# usb_HUB.net
KiCad netlist of a schematic drawn in Altium Designer
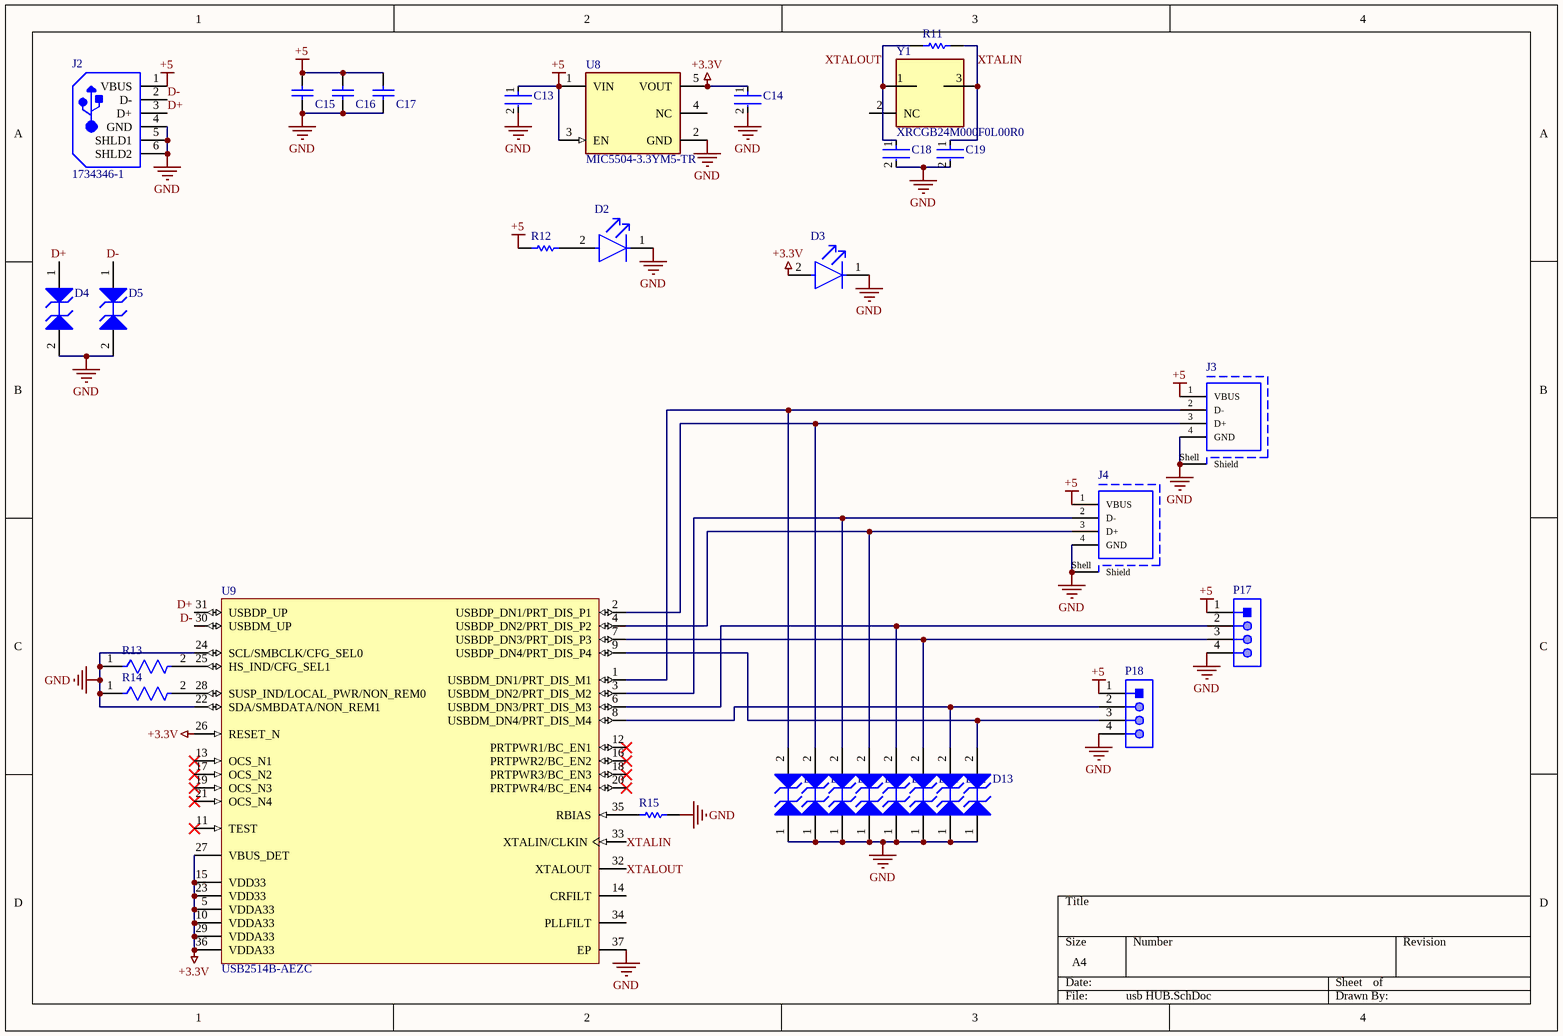
[diagram p0: usb HUB.SchDoc]

(export (version "E")
  (design (tool "Eeschema 10.0.6"))
  (components
    (comp (ref "C13")
      (value "CL31B105MAHNNNE")
      (footprint "FP-CL31-IPC_B")
      (description "Cap Ceramic 1uF 25V X7R ±20% SMD 1206 +125°C Embossed T/R")
      (fields (field (name "TOLERANCE") "20%"))
      (libsource (lib "Altium Content Vault") (part "b4654b650e69147ec39a6b967a45e02"))
    )
    (comp (ref "C14")
      (value "CL31B105MAHNNNE")
      (footprint "FP-CL31-IPC_B")
      (description "Cap Ceramic 1uF 25V X7R ±20% SMD 1206 +125°C Embossed T/R")
      (fields (field (name "TOLERANCE") "20%"))
      (libsource (lib "Altium Content Vault") (part "b4654b650e69147ec39a6b967a45e02"))
    )
    (comp (ref "C15")
      (value "12061Z475KAT2A")
      (footprint "CAPC3216X190X50ML20T25")
      (description "Chip Capacitor, 4.7 uF, +/- 10%, 100 V, -55 to 125 degC, 1206 (3216 Metric), RoHS, Tape and Reel")
      (fields (field (name "MANUFACTURER") "AVX"))
      (libsource (lib "Altium Content Vault") (part "CAP-NP-2"))
    )
    (comp (ref "C16")
      (value "12061Z475KAT2A")
      (footprint "CAPC3216X190X50ML20T25")
      (description "Chip Capacitor, 4.7 uF, +/- 10%, 100 V, -55 to 125 degC, 1206 (3216 Metric), RoHS, Tape and Reel")
      (fields (field (name "MANUFACTURER") "AVX"))
      (libsource (lib "Altium Content Vault") (part "CAP-NP-2"))
    )
    (comp (ref "C17")
      (value "12061Z475KAT2A")
      (footprint "CAPC3216X190X50ML20T25")
      (description "Chip Capacitor, 4.7 uF, +/- 10%, 100 V, -55 to 125 degC, 1206 (3216 Metric), RoHS, Tape and Reel")
      (fields (field (name "MANUFACTURER") "AVX"))
      (libsource (lib "Altium Content Vault") (part "CAP-NP-2"))
    )
    (comp (ref "C18")
      (value "GRM31A7U2J180JW31D")
      (footprint "FP-GRM31A-0_2-e0_3_0_95-IPC_B")
      (description "Chip Multilayer Ceramic Capacitors for General Purpose, 1206, 18pF, U2J, -750ppm/°C, 5%, 630V")
      (fields (field (name "TOLERANCE") "5%"))
      (libsource (lib "Altium Content Vault") (part "b4654b650e69147ec39a6b967a45e02"))
    )
    (comp (ref "C19")
      (value "GRM31A7U2J180JW31D")
      (footprint "FP-GRM31A-0_2-e0_3_0_95-IPC_B")
      (description "Chip Multilayer Ceramic Capacitors for General Purpose, 1206, 18pF, U2J, -750ppm/°C, 5%, 630V")
      (fields (field (name "TOLERANCE") "5%"))
      (libsource (lib "Altium Content Vault") (part "b4654b650e69147ec39a6b967a45e02"))
    )
    (comp (ref "D2")
      (value "APTD3216CGCK")
      (footprint "FP-APTD3216CGCK-MFG")
      (description "LED GREEN CLEAR 2SMD")
      (libsource (lib "Altium Content Vault") (part "8706943c75ba83719d021d2fdc84c58"))
    )
    (comp (ref "D3")
      (value "APTD3216CGCK")
      (footprint "FP-APTD3216CGCK-MFG")
      (description "LED GREEN CLEAR 2SMD")
      (libsource (lib "Altium Content Vault") (part "8706943c75ba83719d021d2fdc84c58"))
    )
    (comp (ref "D4")
      (value "ESD9B3.3ST5G")
      (footprint "ONSC-SOD-923-2-514AB-01_V")
      (fields (field (name "MANUFACTURER") "On Semiconductor"))
      (libsource (lib "Altium Content Vault") (part "ONSC-A1A2-2"))
    )
    (comp (ref "D5")
      (value "ESD9B3.3ST5G")
      (footprint "ONSC-SOD-923-2-514AB-01_V")
      (fields (field (name "MANUFACTURER") "On Semiconductor"))
      (libsource (lib "Altium Content Vault") (part "ONSC-A1A2-2"))
    )
    (comp (ref "D6")
      (value "ESD9B3.3ST5G")
      (footprint "ONSC-SOD-923-2-514AB-01_V")
      (fields (field (name "MANUFACTURER") "On Semiconductor"))
      (libsource (lib "Altium Content Vault") (part "ONSC-A1A2-2"))
    )
    (comp (ref "D7")
      (value "ESD9B3.3ST5G")
      (footprint "ONSC-SOD-923-2-514AB-01_V")
      (fields (field (name "MANUFACTURER") "On Semiconductor"))
      (libsource (lib "Altium Content Vault") (part "ONSC-A1A2-2"))
    )
    (comp (ref "D8")
      (value "ESD9B3.3ST5G")
      (footprint "ONSC-SOD-923-2-514AB-01_V")
      (fields (field (name "MANUFACTURER") "On Semiconductor"))
      (libsource (lib "Altium Content Vault") (part "ONSC-A1A2-2"))
    )
    (comp (ref "D9")
      (value "ESD9B3.3ST5G")
      (footprint "ONSC-SOD-923-2-514AB-01_V")
      (fields (field (name "MANUFACTURER") "On Semiconductor"))
      (libsource (lib "Altium Content Vault") (part "ONSC-A1A2-2"))
    )
    (comp (ref "D10")
      (value "ESD9B3.3ST5G")
      (footprint "ONSC-SOD-923-2-514AB-01_V")
      (fields (field (name "MANUFACTURER") "On Semiconductor"))
      (libsource (lib "Altium Content Vault") (part "ONSC-A1A2-2"))
    )
    (comp (ref "D11")
      (value "ESD9B3.3ST5G")
      (footprint "ONSC-SOD-923-2-514AB-01_V")
      (fields (field (name "MANUFACTURER") "On Semiconductor"))
      (libsource (lib "Altium Content Vault") (part "ONSC-A1A2-2"))
    )
    (comp (ref "D12")
      (value "ESD9B3.3ST5G")
      (footprint "ONSC-SOD-923-2-514AB-01_V")
      (fields (field (name "MANUFACTURER") "On Semiconductor"))
      (libsource (lib "Altium Content Vault") (part "ONSC-A1A2-2"))
    )
    (comp (ref "D13")
      (value "ESD9B3.3ST5G")
      (footprint "ONSC-SOD-923-2-514AB-01_V")
      (fields (field (name "MANUFACTURER") "On Semiconductor"))
      (libsource (lib "Altium Content Vault") (part "ONSC-A1A2-2"))
    )
    (comp (ref "J2")
      (value "1734346-1")
      (footprint "TECO-1734346-1_V")
      (description "USB-B Receptacle Connector, Height 10.87 mm, 0 to 50 degC, RoHS, Tray")
      (fields (field (name "MANUFACTURER") "TE Connectivity"))
      (libsource (lib "Altium Content Vault") (part "USB-4-2SHLD"))
    )
    (comp (ref "J3")
      (value "629104190121")
      (footprint "629104190121")
      (description "USB 2.0 Type A Receptacle WR-COM, Horizontal, SMT, Short Type with Pads and Pegs")
      (fields (field (name "MANUFACTURER") "Wurth Elektronik") (field (name "PUBLISHER") "WurthElektronik"))
      (libsource (lib "Altium Content Vault") (part "WE-USB-4-1SHLD"))
    )
    (comp (ref "J4")
      (value "629104190121")
      (footprint "629104190121")
      (description "USB 2.0 Type A Receptacle WR-COM, Horizontal, SMT, Short Type with Pads and Pegs")
      (fields (field (name "MANUFACTURER") "Wurth Elektronik") (field (name "PUBLISHER") "WurthElektronik"))
      (libsource (lib "Altium Content Vault") (part "WE-USB-4-1SHLD"))
    )
    (comp (ref "P17")
      (value "61300411121")
      (footprint "61300411121")
      (description "THT Vertical Pin Header WR-PHD, Pitch 2.54 mm, Single Row, 4 pins")
      (fields (field (name "MANUFACTURER") "Wurth Elektronik") (field (name "PUBLISHER") "WurthElektronik"))
      (libsource (lib "Altium Content Vault") (part "WE-CN-1P-M-R4"))
    )
    (comp (ref "P18")
      (value "61300411121")
      (footprint "61300411121")
      (description "THT Vertical Pin Header WR-PHD, Pitch 2.54 mm, Single Row, 4 pins")
      (fields (field (name "MANUFACTURER") "Wurth Elektronik") (field (name "PUBLISHER") "WurthElektronik"))
      (libsource (lib "Altium Content Vault") (part "WE-CN-1P-M-R4"))
    )
    (comp (ref "R11")
      (value "ERJ-8ENF1004V")
      (footprint "RESC3216X70X50NL05T20")
      (fields (field (name "MANUFACTURER") "Panasonic"))
      (libsource (lib "Altium Content Vault") (part "RES"))
    )
    (comp (ref "R12")
      (value "ERJ8ENF2203V")
      (footprint "RESC3216X70X50LL05T20")
      (fields (field (name "MANUFACTURER") "Panasonic"))
      (libsource (lib "Altium Content Vault") (part "RES"))
    )
    (comp (ref "R13")
      (value "CRCW120656K0FKEA")
      (footprint "FP-CRCW1206-e3-IPC_C")
      (description "RES Thick Film, 56kΩ, 1%, 0.25W, 100ppm/°C, 1206")
      (fields (field (name "TOLERANCE") "1%"))
      (libsource (lib "Altium Content Vault") (part "1029c3af85768c4190bb7ad29bc67b5"))
    )
    (comp (ref "R14")
      (value "CRCW120656K0FKEA")
      (footprint "FP-CRCW1206-e3-IPC_C")
      (description "RES Thick Film, 56kΩ, 1%, 0.25W, 100ppm/°C, 1206")
      (fields (field (name "TOLERANCE") "1%"))
      (libsource (lib "Altium Content Vault") (part "1029c3af85768c4190bb7ad29bc67b5"))
    )
    (comp (ref "R15")
      (value "ERJ-8GEYJ123V")
      (footprint "RESC3216X70X50NL05T20")
      (fields (field (name "MANUFACTURER") "Panasonic"))
      (libsource (lib "Altium Content Vault") (part "RES"))
    )
    (comp (ref "U8")
      (value "MIC5504-3.3YM5-TR")
      (footprint "FP-SOT23-5LD-PL-1-MFG")
      (description "IC REG LINEAR 3.3V 300MA SOT23-5")
      (libsource (lib "Altium Content Vault") (part "96048095611b4a9579e1e315950d302"))
    )
    (comp (ref "U9")
      (value "USB2514B-AEZC")
      (footprint "Components - 28.12.20 - 14.59:MCHP-QFN-36_V")
      (description "USB 2.0 High-Speed Hub Controller, 4 Ports, 3 to 3.6 V, 0 to 85 degC, 36-Pin QFN, RoHS, Tray")
      (fields (field (name "MANUFACTURER") "Microchip"))
      (libsource (lib "Deej Board") (part "CMP-2000-05217-1"))
    )
    (comp (ref "Y1")
      (value "Crys_Murata_XRCGB24M000F0L00R0_eec")
      (footprint "Crys_Murata_XRCGB24M000F0L00R0_eec_0:Murata_XRCGB24M000F0L00R0_0")
      (description "CRYS 24MHz ±100ppm Crystal 6pF 150 Ohm -30°C ~ 85°C Surface Mount 4-SMD, No Lead")
      (fields
        (field (name "MANUFACTURER") "Murata")
        (field (name "MOUSER PART NUMBER") "81-XRCGB24M000F0L0R0")
        (field (name "PART NUMBER") "XRCGB24M000F0L00R0")
      )
      (libsource (lib "Crys_Murata_XRCGB24M000F0L00R0_eec") (part "Crys_Murata_XRCGB24M000F0L00R0_eec"))
    )
  )
  (nets
    (net (code "1") (name "+3.3V") (class "Default")
      (node (ref "C14") (pin "1") (pinfunction "1_1") (pintype "passive"))
      (node (ref "D3") (pin "2") (pinfunction "A_2") (pintype "passive"))
      (node (ref "U8") (pin "5") (pinfunction "VOUT_5") (pintype "power_in"))
      (node (ref "U9") (pin "10") (pinfunction "VDDA33_10") (pintype "power_in"))
      (node (ref "U9") (pin "15") (pinfunction "VDD33_15") (pintype "power_in"))
      (node (ref "U9") (pin "23") (pinfunction "VDD33_23") (pintype "power_in"))
      (node (ref "U9") (pin "26") (pinfunction "RESET_N_26") (pintype "input"))
      (node (ref "U9") (pin "27") (pinfunction "VBUS_DET_27") (pintype "power_in"))
      (node (ref "U9") (pin "29") (pinfunction "VDDA33_29") (pintype "power_in"))
      (node (ref "U9") (pin "36") (pinfunction "VDDA33_36") (pintype "power_in"))
      (node (ref "U9") (pin "5") (pinfunction "VDDA33_5") (pintype "power_in"))
    )
    (net (code "2") (name "+5") (class "Default")
      (node (ref "C13") (pin "1") (pinfunction "1_1") (pintype "passive"))
      (node (ref "C15") (pin "1") (pinfunction "1_1") (pintype "passive"))
      (node (ref "C16") (pin "1") (pinfunction "1_1") (pintype "passive"))
      (node (ref "C17") (pin "1") (pinfunction "1_1") (pintype "passive"))
      (node (ref "J2") (pin "1") (pinfunction "VBUS_1") (pintype "passive"))
      (node (ref "J3") (pin "1") (pinfunction "VBUS_1") (pintype "passive"))
      (node (ref "J4") (pin "1") (pinfunction "VBUS_1") (pintype "passive"))
      (node (ref "P17") (pin "1") (pinfunction "1_1") (pintype "passive"))
      (node (ref "P18") (pin "1") (pinfunction "1_1") (pintype "passive"))
      (node (ref "R12") (pin "1") (pinfunction "1_1") (pintype "passive"))
      (node (ref "U8") (pin "1") (pinfunction "VIN_1") (pintype "power_in"))
      (node (ref "U8") (pin "3") (pinfunction "EN_3") (pintype "input"))
    )
    (net (code "3") (name "/D+") (class "Default")
      (node (ref "D4") (pin "1") (pinfunction "A1_1") (pintype "passive"))
      (node (ref "J2") (pin "3") (pinfunction "D+_3") (pintype "passive"))
      (node (ref "U9") (pin "31") (pinfunction "USBDP_UP_31") (pintype "bidirectional"))
    )
    (net (code "4") (name "/D-") (class "Default")
      (node (ref "D5") (pin "1") (pinfunction "A1_1") (pintype "passive"))
      (node (ref "J2") (pin "2") (pinfunction "D-_2") (pintype "passive"))
      (node (ref "U9") (pin "30") (pinfunction "USBDM_UP_30") (pintype "bidirectional"))
    )
    (net (code "5") (name "/XTALIN") (class "Default")
      (node (ref "C19") (pin "1") (pinfunction "1_1") (pintype "passive"))
      (node (ref "R11") (pin "2") (pinfunction "2_2") (pintype "passive"))
      (node (ref "U9") (pin "33") (pinfunction "XTALIN/CLKIN_33") (pintype "input"))
      (node (ref "Y1") (pin "3") (pinfunction "2_Crystal_Terminal_3") (pintype "passive"))
    )
    (net (code "6") (name "/XTALOUT") (class "Default")
      (node (ref "C18") (pin "1") (pinfunction "1_1") (pintype "passive"))
      (node (ref "R11") (pin "1") (pinfunction "1_1") (pintype "passive"))
      (node (ref "U9") (pin "32") (pinfunction "XTALOUT_32") (pintype "passive"))
      (node (ref "Y1") (pin "1") (pinfunction "1_Crystal_Terminal_1") (pintype "passive"))
    )
    (net (code "7") (name "GND") (class "Default")
      (node (ref "C13") (pin "2") (pinfunction "2_2") (pintype "passive"))
      (node (ref "C14") (pin "2") (pinfunction "2_2") (pintype "passive"))
      (node (ref "C15") (pin "2") (pinfunction "2_2") (pintype "passive"))
      (node (ref "C16") (pin "2") (pinfunction "2_2") (pintype "passive"))
      (node (ref "C17") (pin "2") (pinfunction "2_2") (pintype "passive"))
      (node (ref "C18") (pin "2") (pinfunction "2_2") (pintype "passive"))
      (node (ref "C19") (pin "2") (pinfunction "2_2") (pintype "passive"))
      (node (ref "D10") (pin "1") (pinfunction "A1_1") (pintype "passive"))
      (node (ref "D11") (pin "1") (pinfunction "A1_1") (pintype "passive"))
      (node (ref "D12") (pin "1") (pinfunction "A1_1") (pintype "passive"))
      (node (ref "D13") (pin "1") (pinfunction "A1_1") (pintype "passive"))
      (node (ref "D2") (pin "1") (pinfunction "C_1") (pintype "passive"))
      (node (ref "D3") (pin "1") (pinfunction "C_1") (pintype "passive"))
      (node (ref "D4") (pin "2") (pinfunction "A2_2") (pintype "passive"))
      (node (ref "D5") (pin "2") (pinfunction "A2_2") (pintype "passive"))
      (node (ref "D6") (pin "1") (pinfunction "A1_1") (pintype "passive"))
      (node (ref "D7") (pin "1") (pinfunction "A1_1") (pintype "passive"))
      (node (ref "D8") (pin "1") (pinfunction "A1_1") (pintype "passive"))
      (node (ref "D9") (pin "1") (pinfunction "A1_1") (pintype "passive"))
      (node (ref "J2") (pin "4") (pinfunction "GND_4") (pintype "passive"))
      (node (ref "J2") (pin "5") (pinfunction "SHLD1_5") (pintype "passive"))
      (node (ref "J2") (pin "6") (pinfunction "SHLD2_6") (pintype "passive"))
      (node (ref "J3") (pin "4") (pinfunction "GND_4") (pintype "passive"))
      (node (ref "J3") (pin "Shell") (pinfunction "Shield_Shell") (pintype "passive"))
      (node (ref "J4") (pin "4") (pinfunction "GND_4") (pintype "passive"))
      (node (ref "J4") (pin "Shell") (pinfunction "Shield_Shell") (pintype "passive"))
      (node (ref "P17") (pin "4") (pinfunction "4_4") (pintype "passive"))
      (node (ref "P18") (pin "4") (pinfunction "4_4") (pintype "passive"))
      (node (ref "R13") (pin "1") (pinfunction "1_1") (pintype "passive"))
      (node (ref "R14") (pin "1") (pinfunction "1_1") (pintype "passive"))
      (node (ref "R15") (pin "2") (pinfunction "2_2") (pintype "passive"))
      (node (ref "U8") (pin "2") (pinfunction "GND_2") (pintype "power_in"))
      (node (ref "U9") (pin "22") (pinfunction "SDA/SMBDATA/NON_REM1_22") (pintype "bidirectional"))
      (node (ref "U9") (pin "24") (pinfunction "SCL/SMBCLK/CFG_SEL0_24") (pintype "bidirectional"))
      (node (ref "U9") (pin "37") (pinfunction "EP_37") (pintype "power_in"))
    )
    (net (code "8") (name "Net-(D2-A)") (class "Default")
      (node (ref "D2") (pin "2") (pinfunction "A_2") (pintype "passive"))
      (node (ref "R12") (pin "2") (pinfunction "2_2") (pintype "passive"))
    )
    (net (code "9") (name "Net-(D6-A2)") (class "Default")
      (node (ref "D6") (pin "2") (pinfunction "A2_2") (pintype "passive"))
      (node (ref "J3") (pin "2") (pinfunction "D-_2") (pintype "passive"))
      (node (ref "U9") (pin "1") (pinfunction "USBDM_DN1/PRT_DIS_M1_1") (pintype "bidirectional"))
    )
    (net (code "10") (name "Net-(D7-A2)") (class "Default")
      (node (ref "D7") (pin "2") (pinfunction "A2_2") (pintype "passive"))
      (node (ref "J3") (pin "3") (pinfunction "D+_3") (pintype "passive"))
      (node (ref "U9") (pin "2") (pinfunction "USBDP_DN1/PRT_DIS_P1_2") (pintype "bidirectional"))
    )
    (net (code "11") (name "Net-(D8-A2)") (class "Default")
      (node (ref "D8") (pin "2") (pinfunction "A2_2") (pintype "passive"))
      (node (ref "J4") (pin "2") (pinfunction "D-_2") (pintype "passive"))
      (node (ref "U9") (pin "3") (pinfunction "USBDM_DN2/PRT_DIS_M2_3") (pintype "bidirectional"))
    )
    (net (code "12") (name "Net-(D9-A2)") (class "Default")
      (node (ref "D9") (pin "2") (pinfunction "A2_2") (pintype "passive"))
      (node (ref "J4") (pin "3") (pinfunction "D+_3") (pintype "passive"))
      (node (ref "U9") (pin "4") (pinfunction "USBDP_DN2/PRT_DIS_P2_4") (pintype "bidirectional"))
    )
    (net (code "13") (name "Net-(D10-A2)") (class "Default")
      (node (ref "D10") (pin "2") (pinfunction "A2_2") (pintype "passive"))
      (node (ref "P17") (pin "2") (pinfunction "2_2") (pintype "passive"))
      (node (ref "U9") (pin "6") (pinfunction "USBDM_DN3/PRT_DIS_M3_6") (pintype "bidirectional"))
    )
    (net (code "14") (name "Net-(D11-A2)") (class "Default")
      (node (ref "D11") (pin "2") (pinfunction "A2_2") (pintype "passive"))
      (node (ref "P17") (pin "3") (pinfunction "3_3") (pintype "passive"))
      (node (ref "U9") (pin "7") (pinfunction "USBDP_DN3/PRT_DIS_P3_7") (pintype "bidirectional"))
    )
    (net (code "15") (name "Net-(D12-A2)") (class "Default")
      (node (ref "D12") (pin "2") (pinfunction "A2_2") (pintype "passive"))
      (node (ref "P18") (pin "2") (pinfunction "2_2") (pintype "passive"))
      (node (ref "U9") (pin "8") (pinfunction "USBDM_DN4/PRT_DIS_M4_8") (pintype "bidirectional"))
    )
    (net (code "16") (name "Net-(D13-A2)") (class "Default")
      (node (ref "D13") (pin "2") (pinfunction "A2_2") (pintype "passive"))
      (node (ref "P18") (pin "3") (pinfunction "3_3") (pintype "passive"))
      (node (ref "U9") (pin "9") (pinfunction "USBDP_DN4/PRT_DIS_P4_9") (pintype "bidirectional"))
    )
    (net (code "17") (name "Net-(U9-HS_IND{slash}CFG_SEL1)") (class "Default")
      (node (ref "R13") (pin "2") (pinfunction "2_2") (pintype "passive"))
      (node (ref "U9") (pin "25") (pinfunction "HS_IND/CFG_SEL1_25") (pintype "bidirectional"))
    )
    (net (code "18") (name "Net-(U9-RBIAS)") (class "Default")
      (node (ref "R15") (pin "1") (pinfunction "1_1") (pintype "passive"))
      (node (ref "U9") (pin "35") (pinfunction "RBIAS_35") (pintype "input"))
    )
    (net (code "19") (name "Net-(U9-SUSP_IND{slash}LOCAL_PWR{slash}NON_REM0)") (class "Default")
      (node (ref "R14") (pin "2") (pinfunction "2_2") (pintype "passive"))
      (node (ref "U9") (pin "28") (pinfunction "SUSP_IND/LOCAL_PWR/NON_REM0_28") (pintype "bidirectional"))
    )
    (net (code "20") (name "unconnected-(U8-NC-Pad4)") (class "Default")
      (node (ref "U8") (pin "4") (pinfunction "NC_4") (pintype "passive"))
    )
    (net (code "21") (name "unconnected-(U9-CRFILT-Pad14)") (class "Default")
      (node (ref "U9") (pin "14") (pinfunction "CRFILT_14") (pintype "passive"))
    )
    (net (code "22") (name "unconnected-(U9-OCS_N1-Pad13)") (class "Default")
      (node (ref "U9") (pin "13") (pinfunction "OCS_N1_13") (pintype "input+no_connect"))
    )
    (net (code "23") (name "unconnected-(U9-OCS_N2-Pad17)") (class "Default")
      (node (ref "U9") (pin "17") (pinfunction "OCS_N2_17") (pintype "input+no_connect"))
    )
    (net (code "24") (name "unconnected-(U9-OCS_N3-Pad19)") (class "Default")
      (node (ref "U9") (pin "19") (pinfunction "OCS_N3_19") (pintype "input+no_connect"))
    )
    (net (code "25") (name "unconnected-(U9-OCS_N4-Pad21)") (class "Default")
      (node (ref "U9") (pin "21") (pinfunction "OCS_N4_21") (pintype "input+no_connect"))
    )
    (net (code "26") (name "unconnected-(U9-PLLFILT-Pad34)") (class "Default")
      (node (ref "U9") (pin "34") (pinfunction "PLLFILT_34") (pintype "passive"))
    )
    (net (code "27") (name "unconnected-(U9-PRTPWR1{slash}BC_EN1-Pad12)") (class "Default")
      (node (ref "U9") (pin "12") (pinfunction "PRTPWR1/BC_EN1_12") (pintype "bidirectional+no_connect"))
    )
    (net (code "28") (name "unconnected-(U9-PRTPWR2{slash}BC_EN2-Pad16)") (class "Default")
      (node (ref "U9") (pin "16") (pinfunction "PRTPWR2/BC_EN2_16") (pintype "bidirectional+no_connect"))
    )
    (net (code "29") (name "unconnected-(U9-PRTPWR3{slash}BC_EN3-Pad18)") (class "Default")
      (node (ref "U9") (pin "18") (pinfunction "PRTPWR3/BC_EN3_18") (pintype "bidirectional+no_connect"))
    )
    (net (code "30") (name "unconnected-(U9-PRTPWR4{slash}BC_EN4-Pad20)") (class "Default")
      (node (ref "U9") (pin "20") (pinfunction "PRTPWR4/BC_EN4_20") (pintype "bidirectional+no_connect"))
    )
    (net (code "31") (name "unconnected-(U9-TEST-Pad11)") (class "Default")
      (node (ref "U9") (pin "11") (pinfunction "TEST_11") (pintype "input+no_connect"))
    )
    (net (code "32") (name "unconnected-(Y1-NC-Pad2)") (class "Default")
      (node (ref "Y1") (pin "2") (pinfunction "NC_2") (pintype "passive"))
    )
  )
)
